# ntp-clock.net
KiCad netlist of a schematic drawn in EAGLE
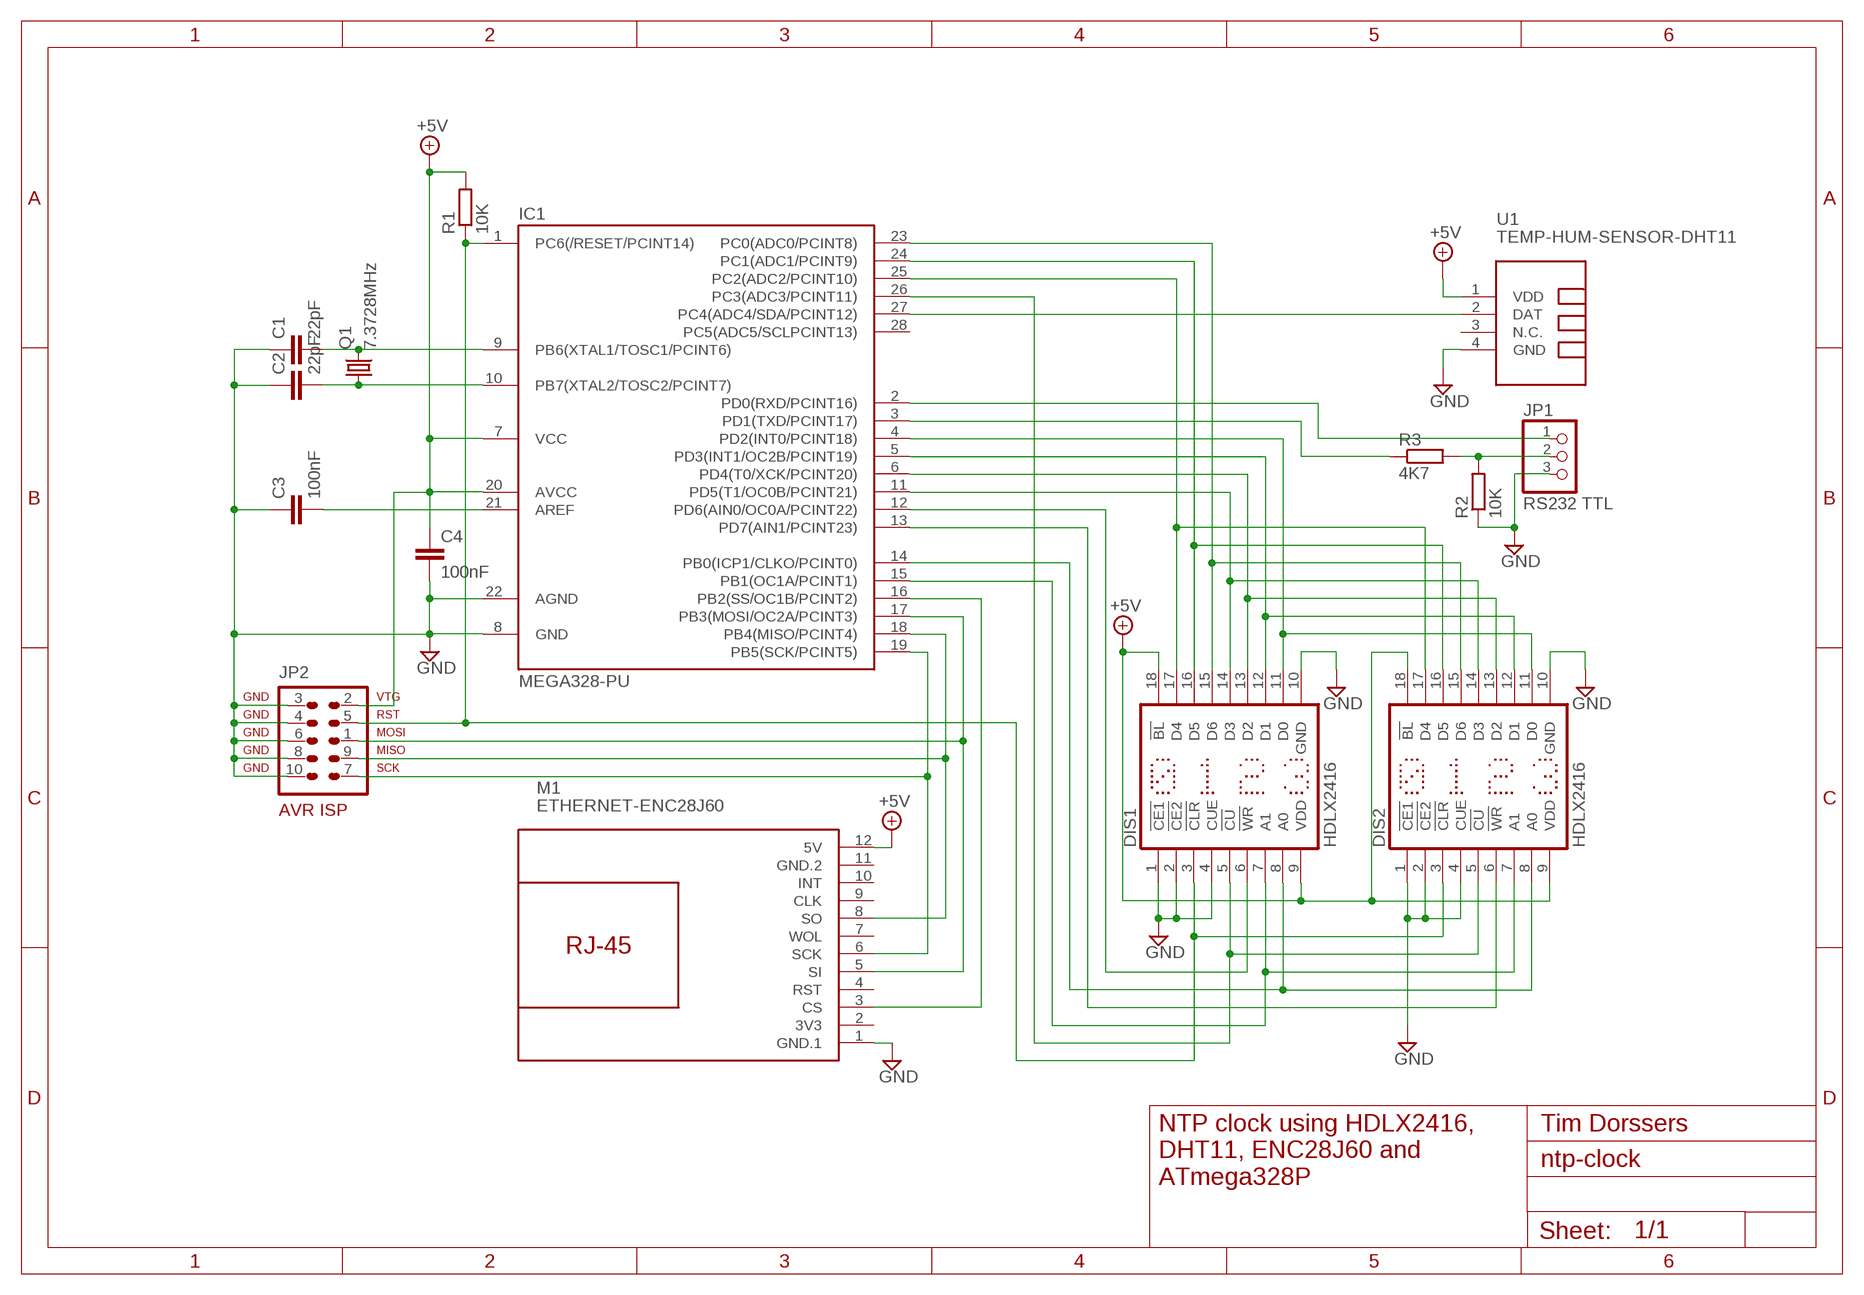
[diagram p0: schematic, sheet 1]

(export (version "E")
  (design (tool "Eeschema 10.0.6"))
  (components
    (comp (ref "C1")
      (value "22pF")
      (footprint "eagle-import:C025-024X044")
      (libsource (lib "eagle-import") (part "C-EU025-024X044"))
    )
    (comp (ref "C2")
      (value "22pF")
      (footprint "eagle-import:C025-024X044")
      (libsource (lib "eagle-import") (part "C-EU025-024X044"))
    )
    (comp (ref "C3")
      (value "100nF")
      (footprint "eagle-import:C025-025X050")
      (libsource (lib "eagle-import") (part "C-EU025-025X050"))
    )
    (comp (ref "C4")
      (value "100nF")
      (footprint "eagle-import:C025-025X050")
      (libsource (lib "eagle-import") (part "C-EU025-025X050"))
    )
    (comp (ref "DIS1")
      (value "HDLX2416")
      (footprint "eagle-import:HDLX2416")
      (libsource (lib "eagle-import") (part "HDLX2416"))
    )
    (comp (ref "DIS2")
      (value "HDLX2416")
      (footprint "eagle-import:HDLX2416")
      (libsource (lib "eagle-import") (part "HDLX2416"))
    )
    (comp (ref "IC1")
      (value "MEGA328-PU")
      (footprint "eagle-import:DIL28-3")
      (libsource (lib "eagle-import") (part "MEGA48/88/168-PU"))
    )
    (comp (ref "JP1")
      (value "RS232 TTL")
      (footprint "eagle-import:1X03")
      (libsource (lib "eagle-import") (part "PINHD-1X3"))
    )
    (comp (ref "JP2")
      (value "AVR-ISP-10")
      (footprint "eagle-import:AVR-ISP-10")
      (libsource (lib "eagle-import") (part "AVR-ISP-10"))
    )
    (comp (ref "M1")
      (value "ETHERNET-ENC28J60")
      (footprint "eagle-import:ETHERNET-ENC28J60")
      (libsource (lib "eagle-import") (part "ETHERNET-ENC28J60"))
    )
    (comp (ref "Q1")
      (value "7.3728MHz")
      (footprint "eagle-import:HC49_S")
      (libsource (lib "eagle-import") (part "CRYSTALHC49S"))
    )
    (comp (ref "R1")
      (value "10K")
      (footprint "eagle-import:0204_7")
      (libsource (lib "eagle-import") (part "R-EU_0204/7"))
    )
    (comp (ref "R2")
      (value "10K")
      (footprint "eagle-import:0204_7")
      (libsource (lib "eagle-import") (part "R-EU_0204/7"))
    )
    (comp (ref "R3")
      (value "4K7")
      (footprint "eagle-import:0204_7")
      (libsource (lib "eagle-import") (part "R-EU_0204/7"))
    )
    (comp (ref "U1")
      (value "TEMP-HUM-SENSOR-DHT11")
      (footprint "eagle-import:TEMP-HUM-SENSOR-DHT11")
      (libsource (lib "eagle-import") (part "TEMP-HUM-SENSOR-DHT11"))
    )
  )
  (nets
    (net (code "1") (name "+5V") (class "Default")
      (node (ref "C4") (pin "1") (pinfunction "1_1") (pintype "passive"))
      (node (ref "DIS1") (pin "18") (pinfunction "~{BL}_18") (pintype "input"))
      (node (ref "DIS1") (pin "9") (pinfunction "VDD_9") (pintype "power_in"))
      (node (ref "DIS2") (pin "18") (pinfunction "~{BL}_18") (pintype "input"))
      (node (ref "DIS2") (pin "9") (pinfunction "VDD_9") (pintype "power_in"))
      (node (ref "IC1") (pin "20") (pinfunction "AVCC_20") (pintype "passive"))
      (node (ref "IC1") (pin "7") (pinfunction "VCC_7") (pintype "power_in"))
      (node (ref "JP2") (pin "2") (pinfunction "2_2") (pintype "passive"))
      (node (ref "M1") (pin "12") (pinfunction "5V_12") (pintype "power_in"))
      (node (ref "R1") (pin "2") (pinfunction "2_2") (pintype "passive"))
      (node (ref "U1") (pin "1") (pinfunction "VDD_1") (pintype "power_in"))
    )
    (net (code "2") (name "/3V3") (class "Default")
      (node (ref "M1") (pin "2") (pinfunction "3V3_2") (pintype "power_in"))
    )
    (net (code "3") (name "/GND.2") (class "Default")
      (node (ref "M1") (pin "11") (pinfunction "GND.2_11") (pintype "power_in"))
    )
    (net (code "4") (name "GND") (class "Default")
      (node (ref "C1") (pin "1") (pinfunction "1_1") (pintype "passive"))
      (node (ref "C2") (pin "1") (pinfunction "1_1") (pintype "passive"))
      (node (ref "C3") (pin "1") (pinfunction "1_1") (pintype "passive"))
      (node (ref "C4") (pin "2") (pinfunction "2_2") (pintype "passive"))
      (node (ref "DIS1") (pin "1") (pinfunction "~{CE1}_1") (pintype "input"))
      (node (ref "DIS1") (pin "10") (pinfunction "GND_10") (pintype "power_in"))
      (node (ref "DIS1") (pin "2") (pinfunction "~{CE2}_2") (pintype "input"))
      (node (ref "DIS1") (pin "4") (pinfunction "CUE_4") (pintype "input"))
      (node (ref "DIS2") (pin "1") (pinfunction "~{CE1}_1") (pintype "input"))
      (node (ref "DIS2") (pin "10") (pinfunction "GND_10") (pintype "power_in"))
      (node (ref "DIS2") (pin "2") (pinfunction "~{CE2}_2") (pintype "input"))
      (node (ref "DIS2") (pin "4") (pinfunction "CUE_4") (pintype "input"))
      (node (ref "IC1") (pin "22") (pinfunction "AGND_22") (pintype "power_in"))
      (node (ref "IC1") (pin "8") (pinfunction "GND_8") (pintype "power_in"))
      (node (ref "JP1") (pin "3") (pinfunction "3_3") (pintype "passive"))
      (node (ref "JP2") (pin "10") (pinfunction "10_10") (pintype "passive"))
      (node (ref "JP2") (pin "3") (pinfunction "3_3") (pintype "passive"))
      (node (ref "JP2") (pin "4") (pinfunction "4_4") (pintype "passive"))
      (node (ref "JP2") (pin "6") (pinfunction "6_6") (pintype "passive"))
      (node (ref "JP2") (pin "8") (pinfunction "8_8") (pintype "passive"))
      (node (ref "M1") (pin "1") (pinfunction "GND.1_1") (pintype "power_in"))
      (node (ref "R2") (pin "1") (pinfunction "1_1") (pintype "passive"))
      (node (ref "U1") (pin "4") (pinfunction "GND_4") (pintype "power_in"))
    )
    (net (code "5") (name "Net-(DIS1-A0)") (class "Default")
      (node (ref "DIS1") (pin "8") (pinfunction "A0_8") (pintype "input"))
      (node (ref "DIS2") (pin "8") (pinfunction "A0_8") (pintype "input"))
      (node (ref "IC1") (pin "14") (pinfunction "PB0(ICP1/CLKO/PCINT0)_14") (pintype "bidirectional"))
    )
    (net (code "6") (name "Net-(DIS1-A1)") (class "Default")
      (node (ref "DIS1") (pin "7") (pinfunction "A1_7") (pintype "input"))
      (node (ref "DIS2") (pin "7") (pinfunction "A1_7") (pintype "input"))
      (node (ref "IC1") (pin "15") (pinfunction "PB1(OC1A/PCINT1)_15") (pintype "bidirectional"))
    )
    (net (code "7") (name "Net-(DIS1-D0)") (class "Default")
      (node (ref "DIS1") (pin "11") (pinfunction "D0_11") (pintype "input"))
      (node (ref "DIS2") (pin "11") (pinfunction "D0_11") (pintype "input"))
      (node (ref "IC1") (pin "4") (pinfunction "PD2(INT0/PCINT18)_4") (pintype "bidirectional"))
    )
    (net (code "8") (name "Net-(DIS1-D1)") (class "Default")
      (node (ref "DIS1") (pin "12") (pinfunction "D1_12") (pintype "input"))
      (node (ref "DIS2") (pin "12") (pinfunction "D1_12") (pintype "input"))
      (node (ref "IC1") (pin "5") (pinfunction "PD3(INT1/OC2B/PCINT19)_5") (pintype "bidirectional"))
    )
    (net (code "9") (name "Net-(DIS1-D2)") (class "Default")
      (node (ref "DIS1") (pin "13") (pinfunction "D2_13") (pintype "input"))
      (node (ref "DIS2") (pin "13") (pinfunction "D2_13") (pintype "input"))
      (node (ref "IC1") (pin "6") (pinfunction "PD4(T0/XCK/PCINT20)_6") (pintype "bidirectional"))
    )
    (net (code "10") (name "Net-(DIS1-D3)") (class "Default")
      (node (ref "DIS1") (pin "14") (pinfunction "D3_14") (pintype "input"))
      (node (ref "DIS2") (pin "14") (pinfunction "D3_14") (pintype "input"))
      (node (ref "IC1") (pin "11") (pinfunction "PD5(T1/OC0B/PCINT21)_11") (pintype "bidirectional"))
    )
    (net (code "11") (name "Net-(DIS1-D4)") (class "Default")
      (node (ref "DIS1") (pin "17") (pinfunction "D4_17") (pintype "input"))
      (node (ref "DIS2") (pin "17") (pinfunction "D4_17") (pintype "input"))
      (node (ref "IC1") (pin "25") (pinfunction "PC2(ADC2/PCINT10)_25") (pintype "bidirectional"))
    )
    (net (code "12") (name "Net-(DIS1-D5)") (class "Default")
      (node (ref "DIS1") (pin "16") (pinfunction "D5_16") (pintype "input"))
      (node (ref "DIS2") (pin "16") (pinfunction "D5_16") (pintype "input"))
      (node (ref "IC1") (pin "24") (pinfunction "PC1(ADC1/PCINT9)_24") (pintype "bidirectional"))
    )
    (net (code "13") (name "Net-(DIS1-D6)") (class "Default")
      (node (ref "DIS1") (pin "15") (pinfunction "D6_15") (pintype "input"))
      (node (ref "DIS2") (pin "15") (pinfunction "D6_15") (pintype "input"))
      (node (ref "IC1") (pin "23") (pinfunction "PC0(ADC0/PCINT8)_23") (pintype "bidirectional"))
    )
    (net (code "14") (name "Net-(DIS1-~{CLR})") (class "Default")
      (node (ref "DIS1") (pin "3") (pinfunction "~{CLR}_3") (pintype "input"))
      (node (ref "DIS2") (pin "3") (pinfunction "~{CLR}_3") (pintype "input"))
      (node (ref "IC1") (pin "1") (pinfunction "PC6(/RESET/PCINT14)_1") (pintype "bidirectional"))
      (node (ref "JP2") (pin "5") (pinfunction "5_5") (pintype "passive"))
      (node (ref "R1") (pin "1") (pinfunction "1_1") (pintype "passive"))
    )
    (net (code "15") (name "Net-(DIS1-~{CU})") (class "Default")
      (node (ref "DIS1") (pin "5") (pinfunction "~{CU}_5") (pintype "input"))
      (node (ref "DIS2") (pin "5") (pinfunction "~{CU}_5") (pintype "input"))
      (node (ref "IC1") (pin "26") (pinfunction "PC3(ADC3/PCINT11)_26") (pintype "bidirectional"))
    )
    (net (code "16") (name "Net-(DIS1-~{WR})") (class "Default")
      (node (ref "DIS1") (pin "6") (pinfunction "~{WR}_6") (pintype "input"))
      (node (ref "IC1") (pin "12") (pinfunction "PD6(AIN0/OC0A/PCINT22)_12") (pintype "bidirectional"))
    )
    (net (code "17") (name "Net-(DIS2-~{WR})") (class "Default")
      (node (ref "DIS2") (pin "6") (pinfunction "~{WR}_6") (pintype "input"))
      (node (ref "IC1") (pin "13") (pinfunction "PD7(AIN1/PCINT23)_13") (pintype "bidirectional"))
    )
    (net (code "18") (name "Net-(IC1-AREF)") (class "Default")
      (node (ref "C3") (pin "2") (pinfunction "2_2") (pintype "passive"))
      (node (ref "IC1") (pin "21") (pinfunction "AREF_21") (pintype "passive"))
    )
    (net (code "19") (name "Net-(IC1-PB2(SS{slash}OC1B{slash}PCINT2))") (class "Default")
      (node (ref "IC1") (pin "16") (pinfunction "PB2(SS/OC1B/PCINT2)_16") (pintype "bidirectional"))
      (node (ref "M1") (pin "3") (pinfunction "CS_3") (pintype "bidirectional"))
    )
    (net (code "20") (name "Net-(IC1-PB3(MOSI{slash}OC2A{slash}PCINT3))") (class "Default")
      (node (ref "IC1") (pin "17") (pinfunction "PB3(MOSI/OC2A/PCINT3)_17") (pintype "bidirectional"))
      (node (ref "JP2") (pin "1") (pinfunction "1_1") (pintype "passive"))
      (node (ref "M1") (pin "5") (pinfunction "SI_5") (pintype "bidirectional"))
    )
    (net (code "21") (name "Net-(IC1-PB4(MISO{slash}PCINT4))") (class "Default")
      (node (ref "IC1") (pin "18") (pinfunction "PB4(MISO/PCINT4)_18") (pintype "bidirectional"))
      (node (ref "JP2") (pin "9") (pinfunction "9_9") (pintype "passive"))
      (node (ref "M1") (pin "8") (pinfunction "SO_8") (pintype "bidirectional"))
    )
    (net (code "22") (name "Net-(IC1-PB5(SCK{slash}PCINT5))") (class "Default")
      (node (ref "IC1") (pin "19") (pinfunction "PB5(SCK/PCINT5)_19") (pintype "bidirectional"))
      (node (ref "JP2") (pin "7") (pinfunction "7_7") (pintype "passive"))
      (node (ref "M1") (pin "6") (pinfunction "SCK_6") (pintype "bidirectional"))
    )
    (net (code "23") (name "Net-(IC1-PB6(XTAL1{slash}TOSC1{slash}PCINT6))") (class "Default")
      (node (ref "C1") (pin "2") (pinfunction "2_2") (pintype "passive"))
      (node (ref "IC1") (pin "9") (pinfunction "PB6(XTAL1/TOSC1/PCINT6)_9") (pintype "bidirectional"))
      (node (ref "Q1") (pin "2") (pinfunction "2_2") (pintype "passive"))
    )
    (net (code "24") (name "Net-(IC1-PB7(XTAL2{slash}TOSC2{slash}PCINT7))") (class "Default")
      (node (ref "C2") (pin "2") (pinfunction "2_2") (pintype "passive"))
      (node (ref "IC1") (pin "10") (pinfunction "PB7(XTAL2/TOSC2/PCINT7)_10") (pintype "bidirectional"))
      (node (ref "Q1") (pin "1") (pinfunction "1_1") (pintype "passive"))
    )
    (net (code "25") (name "Net-(IC1-PC4(ADC4{slash}SDA{slash}PCINT12))") (class "Default")
      (node (ref "IC1") (pin "27") (pinfunction "PC4(ADC4/SDA/PCINT12)_27") (pintype "bidirectional"))
      (node (ref "U1") (pin "2") (pinfunction "DAT_2") (pintype "bidirectional"))
    )
    (net (code "26") (name "Net-(IC1-PD0(RXD{slash}PCINT16))") (class "Default")
      (node (ref "IC1") (pin "2") (pinfunction "PD0(RXD/PCINT16)_2") (pintype "bidirectional"))
      (node (ref "JP1") (pin "1") (pinfunction "1_1") (pintype "passive"))
    )
    (net (code "27") (name "Net-(IC1-PD1(TXD{slash}PCINT17))") (class "Default")
      (node (ref "IC1") (pin "3") (pinfunction "PD1(TXD/PCINT17)_3") (pintype "bidirectional"))
      (node (ref "R3") (pin "1") (pinfunction "1_1") (pintype "passive"))
    )
    (net (code "28") (name "Net-(JP1-Pad2)") (class "Default")
      (node (ref "JP1") (pin "2") (pinfunction "2_2") (pintype "passive"))
      (node (ref "R2") (pin "2") (pinfunction "2_2") (pintype "passive"))
      (node (ref "R3") (pin "2") (pinfunction "2_2") (pintype "passive"))
    )
    (net (code "29") (name "unconnected-(IC1-PC5(ADC5{slash}SCLPCINT13)-Pad28)") (class "Default")
      (node (ref "IC1") (pin "28") (pinfunction "PC5(ADC5/SCLPCINT13)_28") (pintype "bidirectional"))
    )
    (net (code "30") (name "unconnected-(M1-CLK-Pad9)") (class "Default")
      (node (ref "M1") (pin "9") (pinfunction "CLK_9") (pintype "bidirectional"))
    )
    (net (code "31") (name "unconnected-(M1-INT-Pad10)") (class "Default")
      (node (ref "M1") (pin "10") (pinfunction "INT_10") (pintype "bidirectional"))
    )
    (net (code "32") (name "unconnected-(M1-RST-Pad4)") (class "Default")
      (node (ref "M1") (pin "4") (pinfunction "RST_4") (pintype "bidirectional"))
    )
    (net (code "33") (name "unconnected-(M1-WOL-Pad7)") (class "Default")
      (node (ref "M1") (pin "7") (pinfunction "WOL_7") (pintype "bidirectional"))
    )
    (net (code "34") (name "unconnected-(U1-N.C.-Pad3)") (class "Default")
      (node (ref "U1") (pin "3") (pinfunction "N.C._3") (pintype "passive"))
    )
  )
)
